# fish.net
KiCad netlist of a schematic drawn in Altium Designer
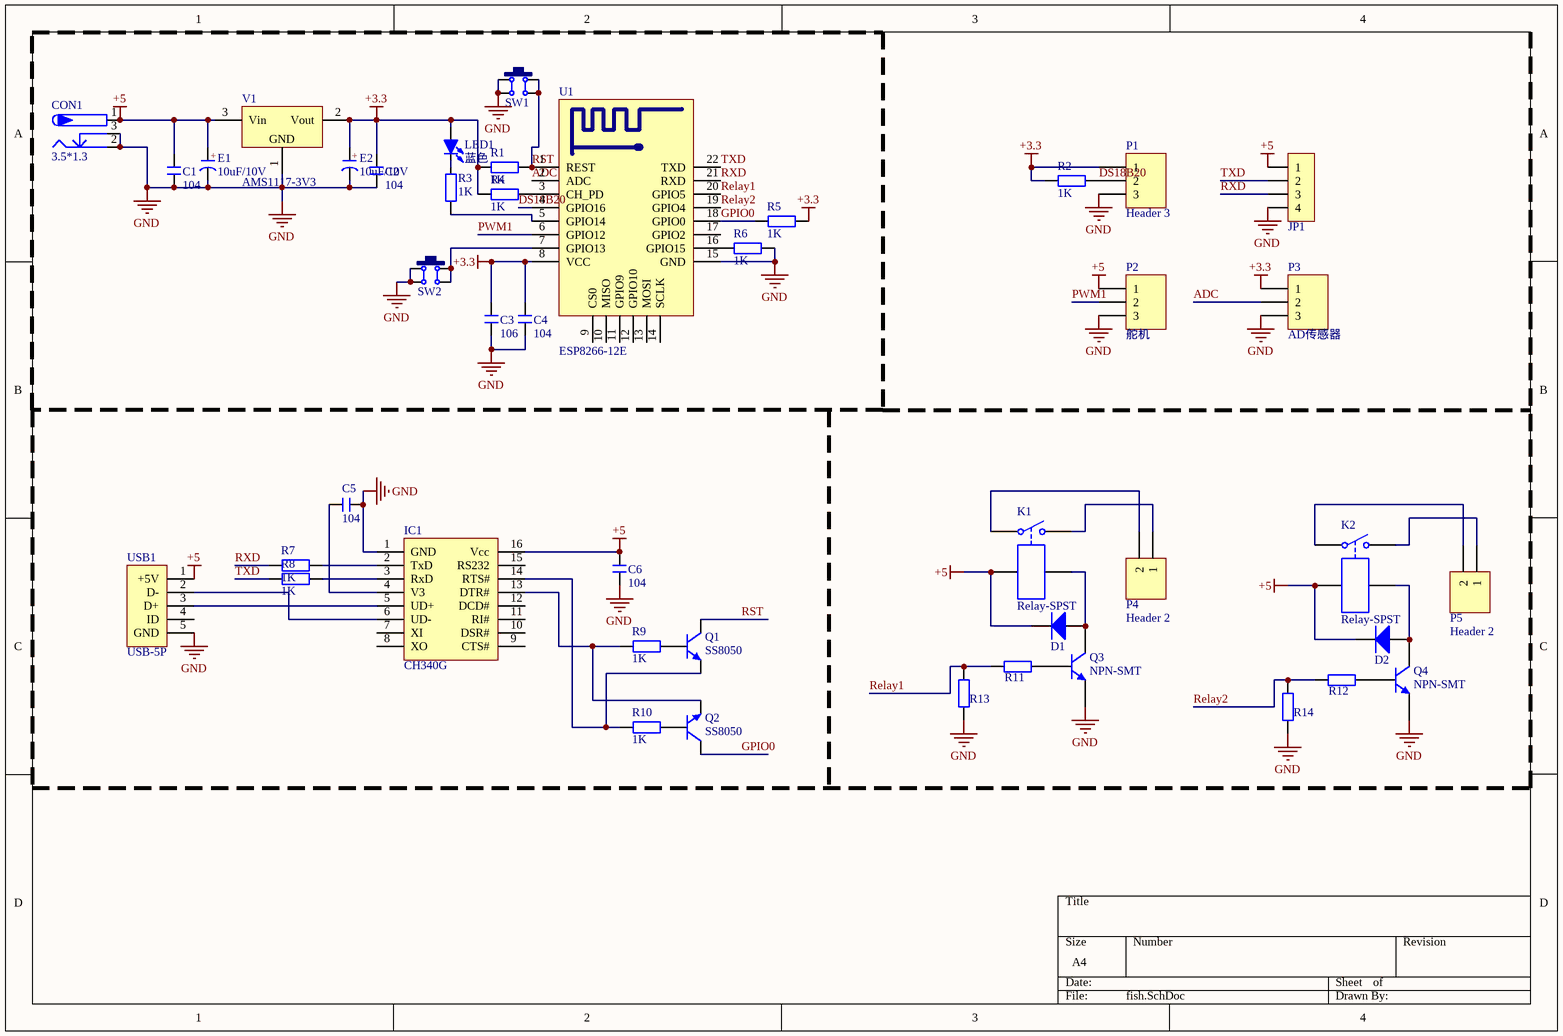
[diagram p0: fish.SchDoc]

(export (version "E")
  (design (tool "Eeschema 10.0.6"))
  (components
    (comp (ref "C1")
      (value "104")
      (footprint "C 0603")
      (description "无极性贴片电容")
      (fields (field (name "版权归属") "黎明电子style"))
      (libsource (lib "电阻-电容-电感") (part "C"))
    )
    (comp (ref "C2")
      (value "104")
      (footprint "C 0603")
      (description "无极性贴片电容")
      (fields (field (name "版权归属") "黎明电子style"))
      (libsource (lib "电阻-电容-电感") (part "C"))
    )
    (comp (ref "C3")
      (value "106")
      (footprint "C 0603")
      (description "无极性贴片电容")
      (fields (field (name "版权归属") "黎明电子style"))
      (libsource (lib "电阻-电容-电感") (part "C"))
    )
    (comp (ref "C4")
      (value "104")
      (footprint "C 0603")
      (description "无极性贴片电容")
      (fields (field (name "版权归属") "黎明电子style"))
      (libsource (lib "电阻-电容-电感") (part "C"))
    )
    (comp (ref "C5")
      (value "104")
      (footprint "C 0603")
      (description "无极性贴片电容")
      (fields (field (name "版权归属") "黎明电子style"))
      (libsource (lib "电阻-电容-电感") (part "C"))
    )
    (comp (ref "C6")
      (value "104")
      (footprint "C 0603")
      (description "无极性贴片电容")
      (fields (field (name "版权归属") "黎明电子style"))
      (libsource (lib "电阻-电容-电感") (part "C"))
    )
    (comp (ref "CON1")
      (value "3.5*1.3")
      (footprint "DC-005")
      (description "低压电源接口")
      (fields (field (name "版权归属") "黎明电子style"))
      (libsource (lib "接口类") (part "P-DC"))
    )
    (comp (ref "D1")
      (value "Diode  Glass")
      (footprint "DSO-C2/X2.3")
      (description "High Conductance Fast Diode")
      (fields (field (name "PUBLISHER") "Altium Limited"))
      (libsource (lib "(NEW)DRC_MD Library") (part "Diode  Glass"))
    )
    (comp (ref "D2")
      (value "Diode  Glass")
      (footprint "DSO-C2/X2.3")
      (description "High Conductance Fast Diode")
      (fields (field (name "PUBLISHER") "Altium Limited"))
      (libsource (lib "(NEW)DRC_MD Library") (part "Diode  Glass"))
    )
    (comp (ref "E1")
      (value "10uF/10V")
      (footprint "CM D(6.3*5.4)")
      (description "贴片电解电容")
      (fields (field (name "版权归属") "黎明电子style"))
      (libsource (lib "电阻-电容-电感") (part "C-CM"))
    )
    (comp (ref "E2")
      (value "10uF/10V")
      (footprint "CM D(6.3*5.4)")
      (description "贴片电解电容")
      (fields (field (name "版权归属") "黎明电子style"))
      (libsource (lib "电阻-电容-电感") (part "C-CM"))
    )
    (comp (ref "IC1")
      (value "CH340G")
      (footprint "SOP16_L")
      (description "串口转USB")
      (fields (field (name "版权归属") "黎明电子style"))
      (libsource (lib "IC芯片") (part "CH340G"))
    )
    (comp (ref "JP1")
      (value "HDR-1X4")
      (footprint "XH2.54-4P")
      (description "4P接插件")
      (fields (field (name "版权归属") "黎明电子style"))
      (libsource (lib "接插件") (part "Header 4"))
    )
    (comp (ref "K1")
      (value "Relay-SPST")
      (footprint "RELAY_HF46F")
      (description "Single-Pole Single-Throw Relay")
      (fields (field (name "PUBLISHER") "Altium Limited"))
      (libsource (lib "(NEW)DRC_MD Library") (part "Relay-SPST"))
    )
    (comp (ref "K2")
      (value "Relay-SPST")
      (footprint "RELAY_HF46F")
      (description "Single-Pole Single-Throw Relay")
      (fields (field (name "PUBLISHER") "Altium Limited"))
      (libsource (lib "(NEW)DRC_MD Library") (part "Relay-SPST"))
    )
    (comp (ref "LED1")
      (value "蓝色")
      (footprint "LED 3MM-B")
      (description "插件LED")
      (fields (field (name "版权归属") "黎明电子style"))
      (libsource (lib "LED") (part "LED-3MM"))
    )
    (comp (ref "P1")
      (value "Header 3")
      (footprint "HX2.54-3")
      (description "Header, 3-Pin")
      (fields (field (name "PUBLISHER") "Altium Limited"))
      (libsource (lib "(NEW)DRC_MD Library") (part "Header 3"))
    )
    (comp (ref "P2")
      (value "舵机")
      (footprint "HX2.54-3")
      (description "Header, 3-Pin")
      (fields (field (name "PUBLISHER") "Altium Limited"))
      (libsource (lib "(NEW)DRC_MD Library") (part "Header 3"))
    )
    (comp (ref "P3")
      (value "AD传感器")
      (footprint "HX2.54-3")
      (description "Header, 3-Pin")
      (fields (field (name "PUBLISHER") "Altium Limited"))
      (libsource (lib "(NEW)DRC_MD Library") (part "Header 3"))
    )
    (comp (ref "P4")
      (value "Header 2")
      (footprint "HX5.08-2L")
      (description "Header, 2-Pin")
      (fields (field (name "PUBLISHER") "Altium Limited"))
      (libsource (lib "(NEW)DRC_MD Library") (part "Header 2"))
    )
    (comp (ref "P5")
      (value "Header 2")
      (footprint "HX5.08-2L")
      (description "Header, 2-Pin")
      (fields (field (name "PUBLISHER") "Altium Limited"))
      (libsource (lib "(NEW)DRC_MD Library") (part "Header 2"))
    )
    (comp (ref "Q1")
      (value "SS8050")
      (footprint "SOT23-3N")
      (description "高频放大-NPN型")
      (fields (field (name "版权归属") "黎明电子style"))
      (libsource (lib "三极管") (part "8050-SMD"))
    )
    (comp (ref "Q2")
      (value "SS8050")
      (footprint "SOT23-3N")
      (description "高频放大-NPN型")
      (fields (field (name "版权归属") "黎明电子style"))
      (libsource (lib "三极管") (part "8050-SMD"))
    )
    (comp (ref "Q3")
      (value "NPN-SMT")
      (footprint "SOT-23")
      (description "NPN Bipolar Transistor")
      (fields (field (name "PUBLISHER") "Altium Limited"))
      (libsource (lib "(NEW)DRC_MD Library") (part "NPN-SMT"))
    )
    (comp (ref "Q4")
      (value "NPN-SMT")
      (footprint "SOT-23")
      (description "NPN Bipolar Transistor")
      (fields (field (name "PUBLISHER") "Altium Limited"))
      (libsource (lib "(NEW)DRC_MD Library") (part "NPN-SMT"))
    )
    (comp (ref "R1")
      (value "1K")
      (footprint "R 0603")
      (description "贴片电阻")
      (fields (field (name "版权归属") "黎明电子style"))
      (libsource (lib "电阻-电容-电感") (part "R"))
    )
    (comp (ref "R2")
      (value "1K")
      (footprint "R 0603")
      (description "贴片电阻")
      (fields (field (name "版权归属") "黎明电子style"))
      (libsource (lib "电阻-电容-电感") (part "R"))
    )
    (comp (ref "R3")
      (value "1K")
      (footprint "R 0603")
      (description "贴片电阻")
      (fields (field (name "版权归属") "黎明电子style"))
      (libsource (lib "电阻-电容-电感") (part "R"))
    )
    (comp (ref "R4")
      (value "1K")
      (footprint "R 0603")
      (description "贴片电阻")
      (fields (field (name "版权归属") "黎明电子style"))
      (libsource (lib "电阻-电容-电感") (part "R"))
    )
    (comp (ref "R5")
      (value "1K")
      (footprint "R 0603")
      (description "贴片电阻")
      (fields (field (name "版权归属") "黎明电子style"))
      (libsource (lib "电阻-电容-电感") (part "R"))
    )
    (comp (ref "R6")
      (value "1K")
      (footprint "R 0603")
      (description "贴片电阻")
      (fields (field (name "版权归属") "黎明电子style"))
      (libsource (lib "电阻-电容-电感") (part "R"))
    )
    (comp (ref "R7")
      (value "1K")
      (footprint "R 0603")
      (description "贴片电阻")
      (fields (field (name "版权归属") "黎明电子style"))
      (libsource (lib "电阻-电容-电感") (part "R"))
    )
    (comp (ref "R8")
      (value "1K")
      (footprint "R 0603")
      (description "贴片电阻")
      (fields (field (name "版权归属") "黎明电子style"))
      (libsource (lib "电阻-电容-电感") (part "R"))
    )
    (comp (ref "R9")
      (value "1K")
      (footprint "R 0603")
      (description "贴片电阻")
      (fields (field (name "版权归属") "黎明电子style"))
      (libsource (lib "电阻-电容-电感") (part "R"))
    )
    (comp (ref "R10")
      (value "1K")
      (footprint "R 0603")
      (description "贴片电阻")
      (fields (field (name "版权归属") "黎明电子style"))
      (libsource (lib "电阻-电容-电感") (part "R"))
    )
    (comp (ref "R11")
      (value "Resistor Chip")
      (footprint "RES_0603")
      (description "Resistor")
      (fields (field (name "PUBLISHER") "Altium Limited"))
      (libsource (lib "") (part "Resistor Chip_1"))
    )
    (comp (ref "R12")
      (value "Resistor Chip")
      (footprint "RES_0603")
      (description "Resistor")
      (fields (field (name "PUBLISHER") "Altium Limited"))
      (libsource (lib "") (part "Resistor Chip_1"))
    )
    (comp (ref "R13")
      (value "Resistor Chip")
      (footprint "RES_0603")
      (description "Resistor")
      (fields (field (name "PUBLISHER") "Altium Limited"))
      (libsource (lib "(NEW)DRC_MD Library") (part "Resistor Chip"))
    )
    (comp (ref "R14")
      (value "Resistor Chip")
      (footprint "RES_0603")
      (description "Resistor")
      (fields (field (name "PUBLISHER") "Altium Limited"))
      (libsource (lib "(NEW)DRC_MD Library") (part "Resistor Chip"))
    )
    (comp (ref "SW1")
      (value "6x6x5")
      (footprint "TSW SMD-6*6*4.3")
      (description "贴片6x6轻触开关")
      (fields (field (name "版权归属") "黎明电子style"))
      (libsource (lib "按键-开关") (part "TSW SMD-6x6"))
    )
    (comp (ref "SW2")
      (value "6x6x5")
      (footprint "TSW SMD-6*6*4.3")
      (description "贴片6x6轻触开关")
      (fields (field (name "版权归属") "黎明电子style"))
      (libsource (lib "按键-开关") (part "TSW SMD-6x6"))
    )
    (comp (ref "U1")
      (value "ESP8266-12E")
      (footprint "ESP_12E")
      (description "串口 WIFI模块，ESP-12E")
      (fields (field (name "版权归属") "黎明电子style"))
      (libsource (lib "模块") (part "ESP8266-12E"))
    )
    (comp (ref "USB1")
      (value "USB-5P")
      (footprint "USB-MICRO_D")
      (description "微型USB母座")
      (fields (field (name "版权归属") "黎明电子style"))
      (libsource (lib "接口类") (part "USB-5P"))
    )
    (comp (ref "V1")
      (value "AMS1117-3V3")
      (footprint "SOT223_L")
      (description "三端稳压芯片")
      (fields (field (name "版权归属") "黎明电子style"))
      (libsource (lib "IC芯片") (part "AMS1117"))
    )
  )
  (nets
    (net (code "1") (name "+3.3") (class "Default")
      (node (ref "C2") (pin "2") (pinfunction "2_2") (pintype "passive"))
      (node (ref "C3") (pin "2") (pinfunction "2_2") (pintype "passive"))
      (node (ref "C4") (pin "2") (pinfunction "2_2") (pintype "passive"))
      (node (ref "E2") (pin "1") (pinfunction "A_1") (pintype "passive"))
      (node (ref "LED1") (pin "1") (pinfunction "A_1") (pintype "passive"))
      (node (ref "P1") (pin "1") (pinfunction "1_1") (pintype "passive"))
      (node (ref "P3") (pin "1") (pinfunction "1_1") (pintype "passive"))
      (node (ref "R1") (pin "1") (pinfunction "1_1") (pintype "passive"))
      (node (ref "R2") (pin "1") (pinfunction "1_1") (pintype "passive"))
      (node (ref "R4") (pin "1") (pinfunction "1_1") (pintype "passive"))
      (node (ref "R5") (pin "2") (pinfunction "2_2") (pintype "passive"))
      (node (ref "U1") (pin "8") (pinfunction "VCC_8") (pintype "passive"))
      (node (ref "V1") (pin "2") (pinfunction "Vout_2") (pintype "passive"))
    )
    (net (code "2") (name "+5") (class "Default")
      (node (ref "C1") (pin "2") (pinfunction "2_2") (pintype "passive"))
      (node (ref "C6") (pin "2") (pinfunction "2_2") (pintype "passive"))
      (node (ref "CON1") (pin "1") (pintype "power_in"))
      (node (ref "D1") (pin "2") (pinfunction "K_2") (pintype "passive"))
      (node (ref "D2") (pin "2") (pinfunction "K_2") (pintype "passive"))
      (node (ref "E1") (pin "1") (pinfunction "A_1") (pintype "passive"))
      (node (ref "IC1") (pin "16") (pinfunction "Vcc_16") (pintype "passive"))
      (node (ref "JP1") (pin "1") (pinfunction "1_1") (pintype "passive"))
      (node (ref "K1") (pin "3") (pinfunction "3_3") (pintype "passive"))
      (node (ref "K2") (pin "3") (pinfunction "3_3") (pintype "passive"))
      (node (ref "P2") (pin "1") (pinfunction "1_1") (pintype "passive"))
      (node (ref "USB1") (pin "1") (pinfunction "+5V_1") (pintype "passive"))
      (node (ref "V1") (pin "3") (pinfunction "Vin_3") (pintype "passive"))
    )
    (net (code "3") (name "/ADC") (class "Default")
      (node (ref "P3") (pin "2") (pinfunction "2_2") (pintype "passive"))
      (node (ref "U1") (pin "2") (pinfunction "ADC_2") (pintype "passive"))
    )
    (net (code "4") (name "/DS18B20") (class "Default")
      (node (ref "P1") (pin "2") (pinfunction "2_2") (pintype "passive"))
      (node (ref "R2") (pin "2") (pinfunction "2_2") (pintype "passive"))
      (node (ref "U1") (pin "4") (pinfunction "GPIO16_4") (pintype "passive"))
    )
    (net (code "5") (name "/GPIO0") (class "Default")
      (node (ref "Q2") (pin "3") (pinfunction "C_3") (pintype "passive"))
      (node (ref "R5") (pin "1") (pinfunction "1_1") (pintype "passive"))
      (node (ref "U1") (pin "18") (pinfunction "GPIO0_18") (pintype "passive"))
    )
    (net (code "6") (name "/PWM1") (class "Default")
      (node (ref "P2") (pin "2") (pinfunction "2_2") (pintype "passive"))
      (node (ref "U1") (pin "6") (pinfunction "GPIO12_6") (pintype "passive"))
    )
    (net (code "7") (name "/RST") (class "Default")
      (node (ref "Q1") (pin "3") (pinfunction "C_3") (pintype "passive"))
      (node (ref "R1") (pin "2") (pinfunction "2_2") (pintype "passive"))
      (node (ref "SW1") (pin "2") (pinfunction "2_2") (pintype "passive"))
      (node (ref "SW1") (pin "3") (pinfunction "3_3") (pintype "passive"))
      (node (ref "U1") (pin "1") (pinfunction "REST_1") (pintype "passive"))
    )
    (net (code "8") (name "/RXD") (class "Default")
      (node (ref "JP1") (pin "3") (pinfunction "3_3") (pintype "passive"))
      (node (ref "R7") (pin "1") (pinfunction "1_1") (pintype "passive"))
      (node (ref "U1") (pin "21") (pinfunction "RXD_21") (pintype "passive"))
    )
    (net (code "9") (name "/Relay1") (class "Default")
      (node (ref "R11") (pin "2") (pinfunction "2_2") (pintype "passive"))
      (node (ref "R13") (pin "2") (pinfunction "2_2") (pintype "passive"))
      (node (ref "U1") (pin "20") (pinfunction "GPIO5_20") (pintype "passive"))
    )
    (net (code "10") (name "/Relay2") (class "Default")
      (node (ref "R12") (pin "2") (pinfunction "2_2") (pintype "passive"))
      (node (ref "R14") (pin "2") (pinfunction "2_2") (pintype "passive"))
      (node (ref "U1") (pin "19") (pinfunction "GPIO4_19") (pintype "passive"))
    )
    (net (code "11") (name "/TXD") (class "Default")
      (node (ref "JP1") (pin "2") (pinfunction "2_2") (pintype "passive"))
      (node (ref "R8") (pin "1") (pinfunction "1_1") (pintype "passive"))
      (node (ref "U1") (pin "22") (pinfunction "TXD_22") (pintype "passive"))
    )
    (net (code "12") (name "GND") (class "Default")
      (node (ref "C1") (pin "1") (pinfunction "1_1") (pintype "passive"))
      (node (ref "C2") (pin "1") (pinfunction "1_1") (pintype "passive"))
      (node (ref "C3") (pin "1") (pinfunction "1_1") (pintype "passive"))
      (node (ref "C4") (pin "1") (pinfunction "1_1") (pintype "passive"))
      (node (ref "C5") (pin "2") (pinfunction "2_2") (pintype "passive"))
      (node (ref "C6") (pin "1") (pinfunction "1_1") (pintype "passive"))
      (node (ref "CON1") (pin "2") (pintype "power_in"))
      (node (ref "CON1") (pin "3") (pintype "power_in"))
      (node (ref "E1") (pin "2") (pinfunction "K_2") (pintype "passive"))
      (node (ref "E2") (pin "2") (pinfunction "K_2") (pintype "passive"))
      (node (ref "IC1") (pin "1") (pinfunction "GND_1") (pintype "passive"))
      (node (ref "JP1") (pin "4") (pinfunction "4_4") (pintype "passive"))
      (node (ref "P1") (pin "3") (pinfunction "3_3") (pintype "passive"))
      (node (ref "P2") (pin "3") (pinfunction "3_3") (pintype "passive"))
      (node (ref "P3") (pin "3") (pinfunction "3_3") (pintype "passive"))
      (node (ref "Q3") (pin "2") (pinfunction "E_2") (pintype "passive"))
      (node (ref "Q4") (pin "2") (pinfunction "E_2") (pintype "passive"))
      (node (ref "R13") (pin "1") (pinfunction "1_1") (pintype "passive"))
      (node (ref "R14") (pin "1") (pinfunction "1_1") (pintype "passive"))
      (node (ref "R6") (pin "2") (pinfunction "2_2") (pintype "passive"))
      (node (ref "SW1") (pin "1") (pinfunction "1_1") (pintype "passive"))
      (node (ref "SW1") (pin "4") (pinfunction "4_4") (pintype "passive"))
      (node (ref "SW2") (pin "1") (pinfunction "1_1") (pintype "passive"))
      (node (ref "SW2") (pin "4") (pinfunction "4_4") (pintype "passive"))
      (node (ref "U1") (pin "15") (pinfunction "GND_15") (pintype "passive"))
      (node (ref "USB1") (pin "5") (pinfunction "GND_5") (pintype "passive"))
      (node (ref "V1") (pin "1") (pinfunction "GND_1") (pintype "passive"))
    )
    (net (code "13") (name "Net-(D1-A)") (class "Default")
      (node (ref "D1") (pin "1") (pinfunction "A_1") (pintype "passive"))
      (node (ref "K1") (pin "4") (pinfunction "4_4") (pintype "passive"))
      (node (ref "Q3") (pin "3") (pinfunction "C_3") (pintype "passive"))
    )
    (net (code "14") (name "Net-(D2-A)") (class "Default")
      (node (ref "D2") (pin "1") (pinfunction "A_1") (pintype "passive"))
      (node (ref "K2") (pin "4") (pinfunction "4_4") (pintype "passive"))
      (node (ref "Q4") (pin "3") (pinfunction "C_3") (pintype "passive"))
    )
    (net (code "15") (name "Net-(IC1-DTR#)") (class "Default")
      (node (ref "IC1") (pin "13") (pinfunction "DTR#_13") (pintype "passive"))
      (node (ref "Q2") (pin "2") (pinfunction "E_2") (pintype "passive"))
      (node (ref "R9") (pin "1") (pinfunction "1_1") (pintype "passive"))
    )
    (net (code "16") (name "Net-(IC1-RTS#)") (class "Default")
      (node (ref "IC1") (pin "14") (pinfunction "RTS#_14") (pintype "passive"))
      (node (ref "Q1") (pin "2") (pinfunction "E_2") (pintype "passive"))
      (node (ref "R10") (pin "1") (pinfunction "1_1") (pintype "passive"))
    )
    (net (code "17") (name "Net-(IC1-RxD)") (class "Default")
      (node (ref "IC1") (pin "3") (pinfunction "RxD_3") (pintype "passive"))
      (node (ref "R8") (pin "2") (pinfunction "2_2") (pintype "passive"))
    )
    (net (code "18") (name "Net-(IC1-TxD)") (class "Default")
      (node (ref "IC1") (pin "2") (pinfunction "TxD_2") (pintype "passive"))
      (node (ref "R7") (pin "2") (pinfunction "2_2") (pintype "passive"))
    )
    (net (code "19") (name "Net-(IC1-UD+)") (class "Default")
      (node (ref "IC1") (pin "5") (pinfunction "UD+_5") (pintype "passive"))
      (node (ref "USB1") (pin "3") (pinfunction "D+_3") (pintype "passive"))
    )
    (net (code "20") (name "Net-(IC1-UD-)") (class "Default")
      (node (ref "IC1") (pin "6") (pinfunction "UD-_6") (pintype "passive"))
      (node (ref "USB1") (pin "2") (pinfunction "D-_2") (pintype "passive"))
    )
    (net (code "21") (name "Net-(IC1-V3)") (class "Default")
      (node (ref "C5") (pin "1") (pinfunction "1_1") (pintype "passive"))
      (node (ref "IC1") (pin "4") (pinfunction "V3_4") (pintype "passive"))
    )
    (net (code "22") (name "Net-(K1-Pad1)") (class "Default")
      (node (ref "K1") (pin "1") (pinfunction "1_1") (pintype "passive"))
      (node (ref "P4") (pin "2") (pinfunction "2_2") (pintype "passive"))
    )
    (net (code "23") (name "Net-(K1-Pad2)") (class "Default")
      (node (ref "K1") (pin "2") (pinfunction "2_2") (pintype "passive"))
      (node (ref "P4") (pin "1") (pinfunction "1_1") (pintype "passive"))
    )
    (net (code "24") (name "Net-(K2-Pad1)") (class "Default")
      (node (ref "K2") (pin "1") (pinfunction "1_1") (pintype "passive"))
      (node (ref "P5") (pin "2") (pinfunction "2_2") (pintype "passive"))
    )
    (net (code "25") (name "Net-(K2-Pad2)") (class "Default")
      (node (ref "K2") (pin "2") (pinfunction "2_2") (pintype "passive"))
      (node (ref "P5") (pin "1") (pinfunction "1_1") (pintype "passive"))
    )
    (net (code "26") (name "Net-(LED1-K)") (class "Default")
      (node (ref "LED1") (pin "2") (pinfunction "K_2") (pintype "passive"))
      (node (ref "R3") (pin "2") (pinfunction "2_2") (pintype "passive"))
    )
    (net (code "27") (name "Net-(Q1-B)") (class "Default")
      (node (ref "Q1") (pin "1") (pinfunction "B_1") (pintype "passive"))
      (node (ref "R9") (pin "2") (pinfunction "2_2") (pintype "passive"))
    )
    (net (code "28") (name "Net-(Q2-B)") (class "Default")
      (node (ref "Q2") (pin "1") (pinfunction "B_1") (pintype "passive"))
      (node (ref "R10") (pin "2") (pinfunction "2_2") (pintype "passive"))
    )
    (net (code "29") (name "Net-(Q3-B)") (class "Default")
      (node (ref "Q3") (pin "1") (pinfunction "B_1") (pintype "passive"))
      (node (ref "R11") (pin "1") (pinfunction "1_1") (pintype "passive"))
    )
    (net (code "30") (name "Net-(Q4-B)") (class "Default")
      (node (ref "Q4") (pin "1") (pinfunction "B_1") (pintype "passive"))
      (node (ref "R12") (pin "1") (pinfunction "1_1") (pintype "passive"))
    )
    (net (code "31") (name "Net-(U1-CH_PD)") (class "Default")
      (node (ref "R4") (pin "2") (pinfunction "2_2") (pintype "passive"))
      (node (ref "U1") (pin "3") (pinfunction "CH_PD_3") (pintype "passive"))
    )
    (net (code "32") (name "Net-(U1-GPIO13)") (class "Default")
      (node (ref "SW2") (pin "2") (pinfunction "2_2") (pintype "passive"))
      (node (ref "SW2") (pin "3") (pinfunction "3_3") (pintype "passive"))
      (node (ref "U1") (pin "7") (pinfunction "GPIO13_7") (pintype "passive"))
    )
    (net (code "33") (name "Net-(U1-GPIO14)") (class "Default")
      (node (ref "R3") (pin "1") (pinfunction "1_1") (pintype "passive"))
      (node (ref "U1") (pin "5") (pinfunction "GPIO14_5") (pintype "passive"))
    )
    (net (code "34") (name "Net-(U1-GPIO15)") (class "Default")
      (node (ref "R6") (pin "1") (pinfunction "1_1") (pintype "passive"))
      (node (ref "U1") (pin "16") (pinfunction "GPIO15_16") (pintype "passive"))
    )
    (net (code "35") (name "unconnected-(IC1-CTS#-Pad9)") (class "Default")
      (node (ref "IC1") (pin "9") (pinfunction "CTS#_9") (pintype "passive"))
    )
    (net (code "36") (name "unconnected-(IC1-DCD#-Pad12)") (class "Default")
      (node (ref "IC1") (pin "12") (pinfunction "DCD#_12") (pintype "passive"))
    )
    (net (code "37") (name "unconnected-(IC1-DSR#-Pad10)") (class "Default")
      (node (ref "IC1") (pin "10") (pinfunction "DSR#_10") (pintype "passive"))
    )
    (net (code "38") (name "unconnected-(IC1-RI#-Pad11)") (class "Default")
      (node (ref "IC1") (pin "11") (pinfunction "RI#_11") (pintype "passive"))
    )
    (net (code "39") (name "unconnected-(IC1-RS232-Pad15)") (class "Default")
      (node (ref "IC1") (pin "15") (pinfunction "RS232_15") (pintype "passive"))
    )
    (net (code "40") (name "unconnected-(IC1-XI-Pad7)") (class "Default")
      (node (ref "IC1") (pin "7") (pinfunction "XI_7") (pintype "passive"))
    )
    (net (code "41") (name "unconnected-(IC1-XO-Pad8)") (class "Default")
      (node (ref "IC1") (pin "8") (pinfunction "XO_8") (pintype "passive"))
    )
    (net (code "42") (name "unconnected-(U1-CS0-Pad9)") (class "Default")
      (node (ref "U1") (pin "9") (pinfunction "CS0_9") (pintype "passive"))
    )
    (net (code "43") (name "unconnected-(U1-GPIO2-Pad17)") (class "Default")
      (node (ref "U1") (pin "17") (pinfunction "GPIO2_17") (pintype "passive"))
    )
    (net (code "44") (name "unconnected-(U1-GPIO9-Pad11)") (class "Default")
      (node (ref "U1") (pin "11") (pinfunction "GPIO9_11") (pintype "passive"))
    )
    (net (code "45") (name "unconnected-(U1-GPIO10-Pad12)") (class "Default")
      (node (ref "U1") (pin "12") (pinfunction "GPIO10_12") (pintype "passive"))
    )
    (net (code "46") (name "unconnected-(U1-MISO-Pad10)") (class "Default")
      (node (ref "U1") (pin "10") (pinfunction "MISO_10") (pintype "passive"))
    )
    (net (code "47") (name "unconnected-(U1-MOSI-Pad13)") (class "Default")
      (node (ref "U1") (pin "13") (pinfunction "MOSI_13") (pintype "passive"))
    )
    (net (code "48") (name "unconnected-(U1-SCLK-Pad14)") (class "Default")
      (node (ref "U1") (pin "14") (pinfunction "SCLK_14") (pintype "passive"))
    )
    (net (code "49") (name "unconnected-(USB1-ID-Pad4)") (class "Default")
      (node (ref "USB1") (pin "4") (pinfunction "ID_4") (pintype "passive"))
    )
  )
)
